# USB.net
KiCad netlist of a schematic drawn in EasyEDA Pro
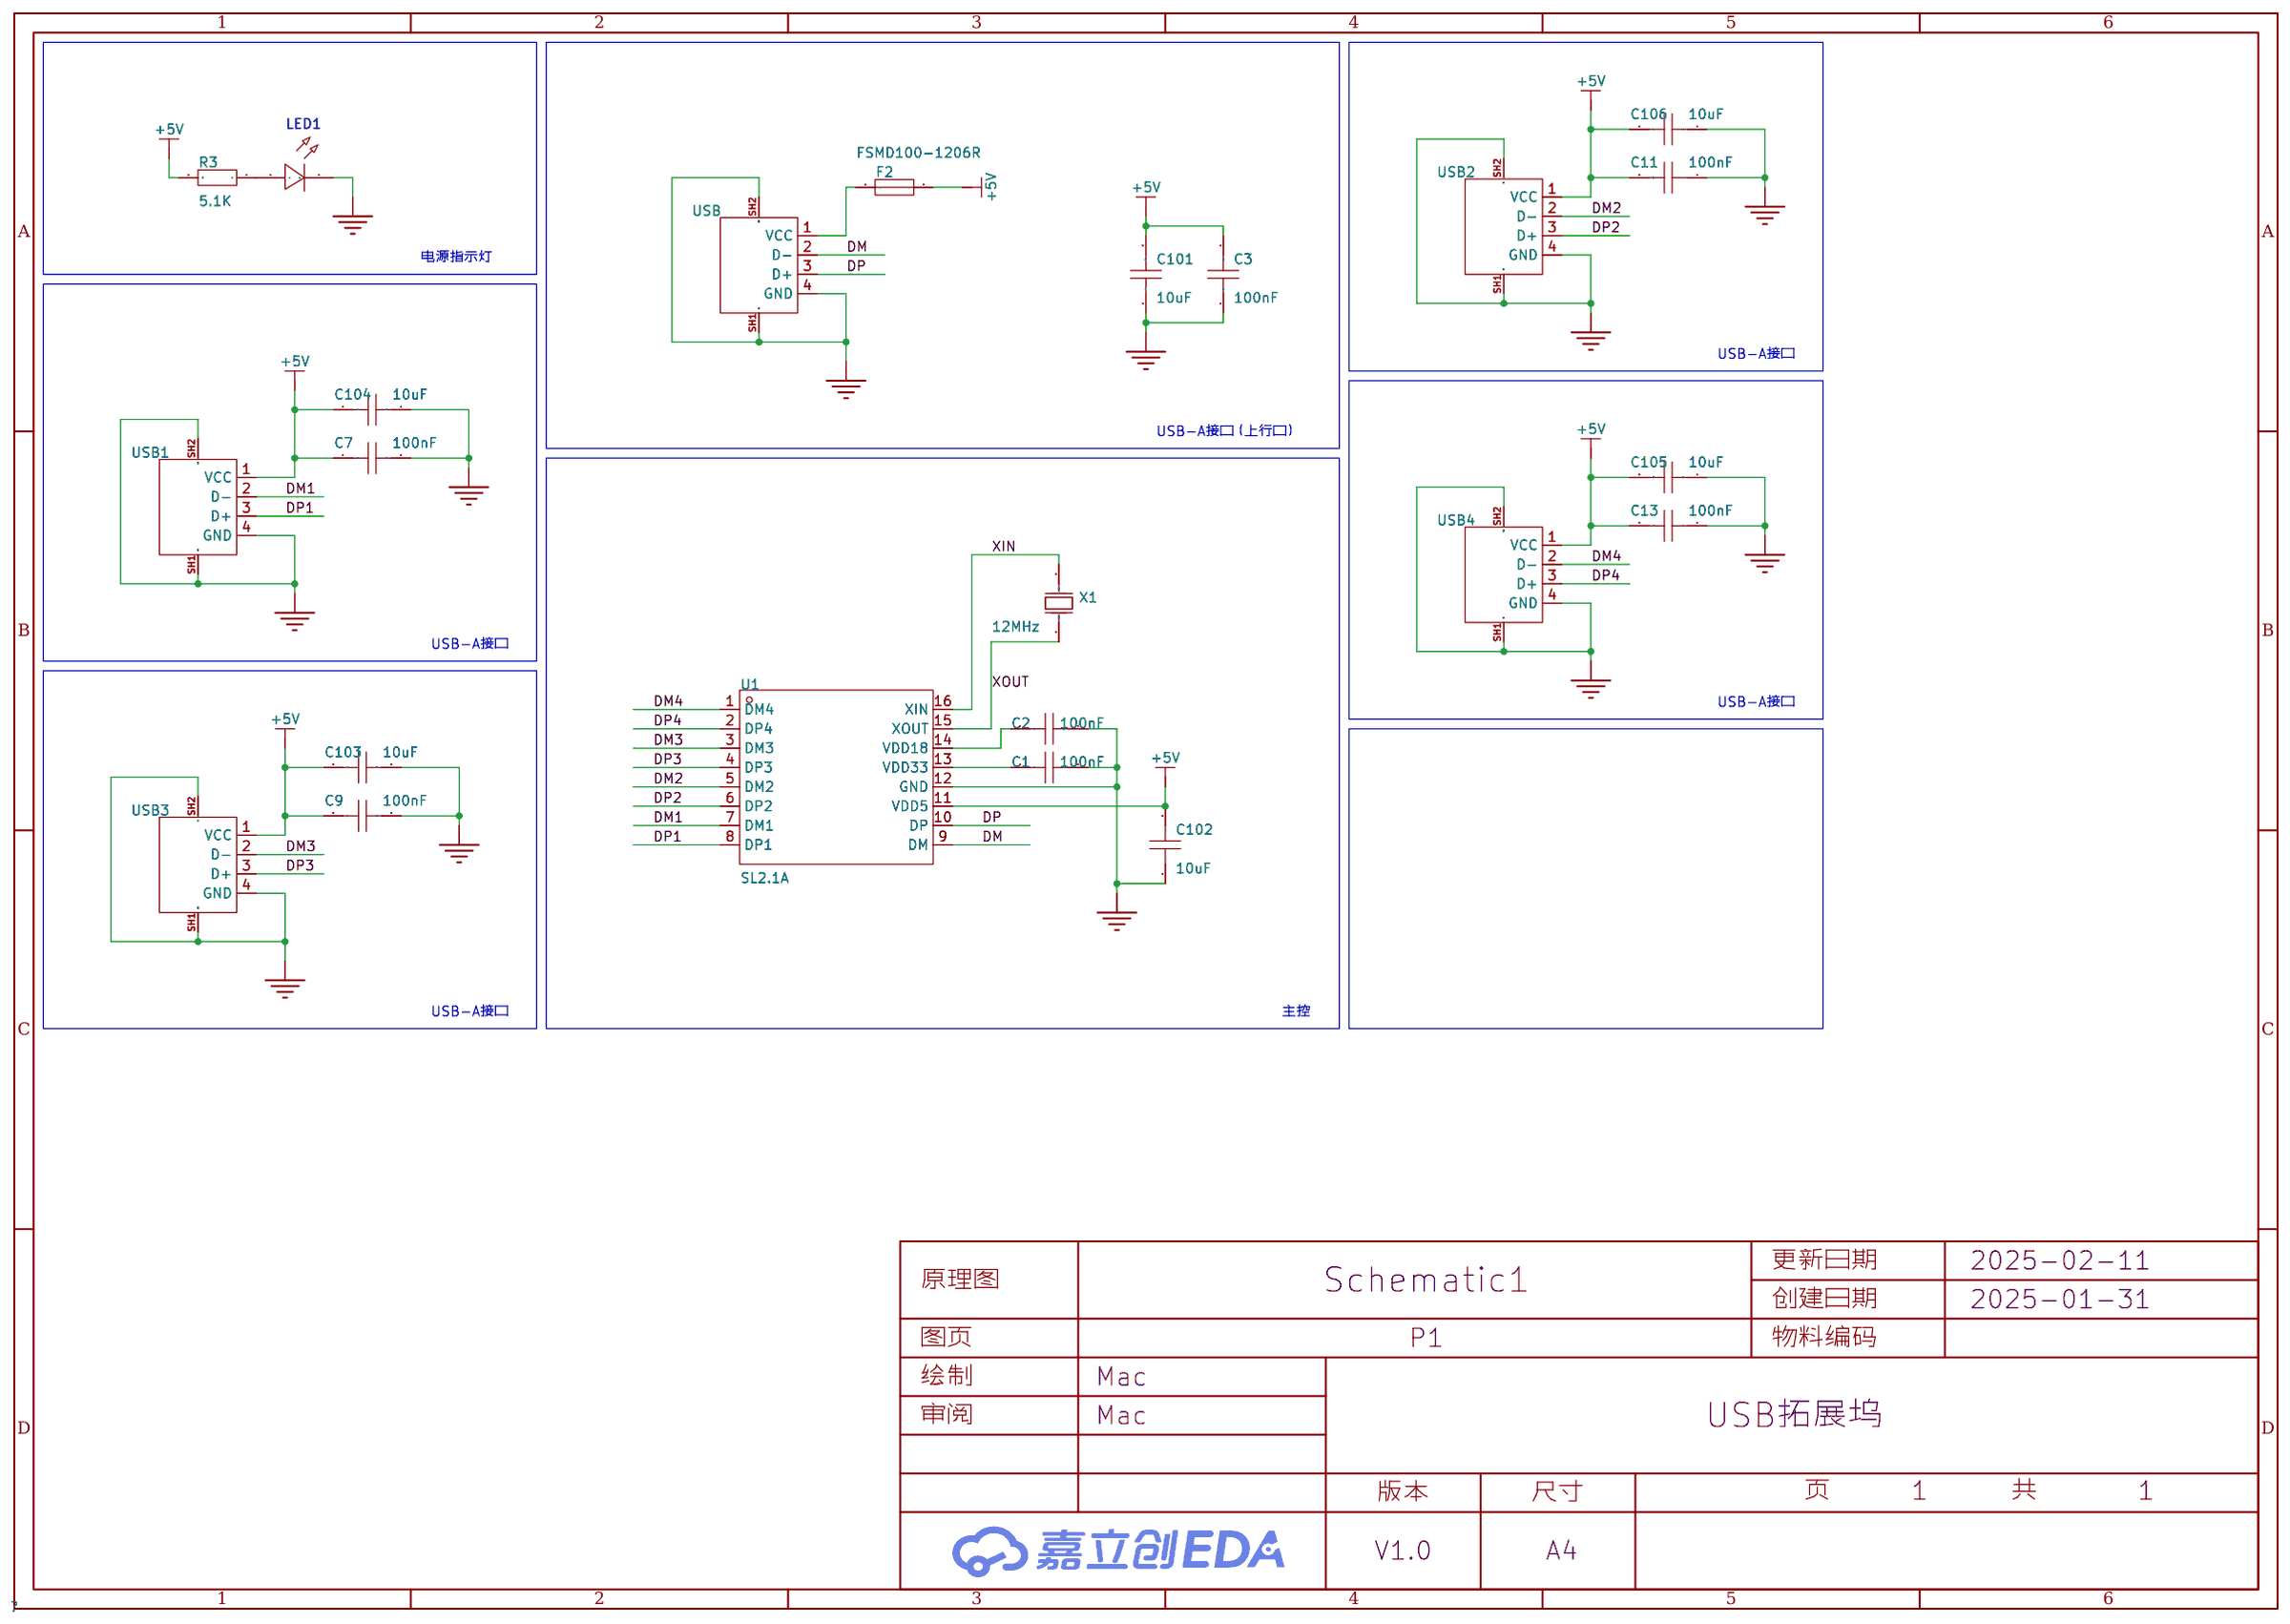
[diagram p0: schematic sheet]

(export (version "E")
  (design (tool "Eeschema 10.0.6"))
  (components
    (comp (ref "C1")
      (value "100nF")
      (footprint "easyedapro:C0603")
      (libsource (lib "easyedapro") (part "CapAcitance"))
    )
    (comp (ref "C2")
      (value "100nF")
      (footprint "easyedapro:C0603")
      (libsource (lib "easyedapro") (part "CapAcitance"))
    )
    (comp (ref "C3")
      (value "100nF")
      (footprint "easyedapro:C0603")
      (libsource (lib "easyedapro") (part "CapAcitance"))
    )
    (comp (ref "C7")
      (value "100nF")
      (footprint "easyedapro:C0603")
      (libsource (lib "easyedapro") (part "CapAcitance"))
    )
    (comp (ref "C9")
      (value "100nF")
      (footprint "easyedapro:C0603")
      (libsource (lib "easyedapro") (part "CapAcitance"))
    )
    (comp (ref "C11")
      (value "100nF")
      (footprint "easyedapro:C0603")
      (libsource (lib "easyedapro") (part "CapAcitance"))
    )
    (comp (ref "C13")
      (value "100nF")
      (footprint "easyedapro:C0603")
      (libsource (lib "easyedapro") (part "CapAcitance"))
    )
    (comp (ref "C101")
      (value "10uF")
      (footprint "easyedapro:C0603")
      (libsource (lib "easyedapro") (part "CapAcitance"))
    )
    (comp (ref "C102")
      (value "10uF")
      (footprint "easyedapro:C0603")
      (libsource (lib "easyedapro") (part "CapAcitance"))
    )
    (comp (ref "C103")
      (value "10uF")
      (footprint "easyedapro:C0603")
      (libsource (lib "easyedapro") (part "CapAcitance"))
    )
    (comp (ref "C104")
      (value "10uF")
      (footprint "easyedapro:C0603")
      (libsource (lib "easyedapro") (part "CapAcitance"))
    )
    (comp (ref "C105")
      (value "10uF")
      (footprint "easyedapro:C0603")
      (libsource (lib "easyedapro") (part "CapAcitance"))
    )
    (comp (ref "C106")
      (value "10uF")
      (footprint "easyedapro:C0603")
      (libsource (lib "easyedapro") (part "CapAcitance"))
    )
    (comp (ref "F2")
      (value "FSMD100-1206R")
      (footprint "easyedapro:F1206")
      (description "最大电压:6V;最大电流:100A;保持电流:1A;跳闸电流:1.8A;")
      (fields (field (name "Manufacturer") "FUZETEC(富致)"))
      (libsource (lib "easyedapro") (part "FSMD100-1206R"))
    )
    (comp (ref "LED1")
      (value "~")
      (footprint "easyedapro:LED_0603")
      (libsource (lib "easyedapro") (part "LED_G"))
    )
    (comp (ref "R3") (value "5.1K") (footprint "easyedapro:R0603") (libsource (lib "easyedapro") (part "电阻")))
    (comp (ref "U1")
      (value "SL2.1A")
      (footprint "easyedapro:SOP-16_L10.0-W3.9-P1.27-LS6.0-BL")
      (description "应用功能:集线器;接口协议:-;")
      (fields (field (name "Manufacturer") "CoreChips(和芯润德)"))
      (libsource (lib "easyedapro") (part "SL2.1A"))
    )
    (comp (ref "USB")
      (value "~")
      (footprint "easyedapro:USB_ Type-A")
      (libsource (lib "easyedapro") (part "USB_Type-A"))
    )
    (comp (ref "USB1")
      (value "~")
      (footprint "easyedapro:USB_ Type-A")
      (libsource (lib "easyedapro") (part "USB_Type-A"))
    )
    (comp (ref "USB2")
      (value "~")
      (footprint "easyedapro:USB_ Type-A")
      (libsource (lib "easyedapro") (part "USB_Type-A"))
    )
    (comp (ref "USB3")
      (value "~")
      (footprint "easyedapro:USB_ Type-A")
      (libsource (lib "easyedapro") (part "USB_Type-A"))
    )
    (comp (ref "USB4")
      (value "~")
      (footprint "easyedapro:USB_ Type-A")
      (libsource (lib "easyedapro") (part "USB_Type-A"))
    )
    (comp (ref "X1")
      (value "12MHz")
      (footprint "easyedapro:HC-49US_L11.5-W4.5-P4.88")
      (description "晶振类型:直插晶振;频率:12MHz;常温频差:±20ppm;外接负载电容:20pF;频率稳定度(全温):±30ppm;")
      (fields (field (name "Manufacturer Part") "X49SD12MSD2SC") (field (name "Manufacturer") "YXC(扬兴晶振)"))
      (libsource (lib "easyedapro") (part "X49SD12MSD2SC"))
    )
  )
  (nets
    (net (code "1") (name "+5V") (class "Default")
      (node (ref "C101") (pin "2") (pinfunction "2_2") (pintype "input"))
      (node (ref "C102") (pin "2") (pinfunction "2_2") (pintype "input"))
      (node (ref "C103") (pin "2") (pinfunction "2_2") (pintype "input"))
      (node (ref "C104") (pin "2") (pinfunction "2_2") (pintype "input"))
      (node (ref "C105") (pin "2") (pinfunction "2_2") (pintype "input"))
      (node (ref "C106") (pin "2") (pinfunction "2_2") (pintype "input"))
      (node (ref "C11") (pin "2") (pinfunction "2_2") (pintype "input"))
      (node (ref "C13") (pin "2") (pinfunction "2_2") (pintype "input"))
      (node (ref "C3") (pin "2") (pinfunction "2_2") (pintype "input"))
      (node (ref "C7") (pin "2") (pinfunction "2_2") (pintype "input"))
      (node (ref "C9") (pin "2") (pinfunction "2_2") (pintype "input"))
      (node (ref "F2") (pin "1") (pinfunction "1_1") (pintype "unspecified"))
      (node (ref "R3") (pin "2") (pinfunction "2_2") (pintype "input"))
      (node (ref "U1") (pin "11") (pinfunction "VDD5_11") (pintype "unspecified"))
      (node (ref "USB1") (pin "1") (pinfunction "VCC_1") (pintype "input"))
      (node (ref "USB2") (pin "1") (pinfunction "VCC_1") (pintype "input"))
      (node (ref "USB3") (pin "1") (pinfunction "VCC_1") (pintype "input"))
      (node (ref "USB4") (pin "1") (pinfunction "VCC_1") (pintype "input"))
    )
    (net (code "2") (name "/DM") (class "Default")
      (node (ref "U1") (pin "9") (pinfunction "DM_9") (pintype "unspecified"))
      (node (ref "USB") (pin "2") (pinfunction "D-_2") (pintype "input"))
    )
    (net (code "3") (name "/DM1") (class "Default")
      (node (ref "U1") (pin "7") (pinfunction "DM1_7") (pintype "unspecified"))
      (node (ref "USB1") (pin "2") (pinfunction "D-_2") (pintype "input"))
    )
    (net (code "4") (name "/DM2") (class "Default")
      (node (ref "U1") (pin "5") (pinfunction "DM2_5") (pintype "unspecified"))
      (node (ref "USB2") (pin "2") (pinfunction "D-_2") (pintype "input"))
    )
    (net (code "5") (name "/DM3") (class "Default")
      (node (ref "U1") (pin "3") (pinfunction "DM3_3") (pintype "unspecified"))
      (node (ref "USB3") (pin "2") (pinfunction "D-_2") (pintype "input"))
    )
    (net (code "6") (name "/DM4") (class "Default")
      (node (ref "U1") (pin "1") (pinfunction "DM4_1") (pintype "unspecified"))
      (node (ref "USB4") (pin "2") (pinfunction "D-_2") (pintype "input"))
    )
    (net (code "7") (name "/DP") (class "Default")
      (node (ref "U1") (pin "10") (pinfunction "DP_10") (pintype "unspecified"))
      (node (ref "USB") (pin "3") (pinfunction "D+_3") (pintype "input"))
    )
    (net (code "8") (name "/DP1") (class "Default")
      (node (ref "U1") (pin "8") (pinfunction "DP1_8") (pintype "unspecified"))
      (node (ref "USB1") (pin "3") (pinfunction "D+_3") (pintype "input"))
    )
    (net (code "9") (name "/DP2") (class "Default")
      (node (ref "U1") (pin "6") (pinfunction "DP2_6") (pintype "unspecified"))
      (node (ref "USB2") (pin "3") (pinfunction "D+_3") (pintype "input"))
    )
    (net (code "10") (name "/DP3") (class "Default")
      (node (ref "U1") (pin "4") (pinfunction "DP3_4") (pintype "unspecified"))
      (node (ref "USB3") (pin "3") (pinfunction "D+_3") (pintype "input"))
    )
    (net (code "11") (name "/DP4") (class "Default")
      (node (ref "U1") (pin "2") (pinfunction "DP4_2") (pintype "unspecified"))
      (node (ref "USB4") (pin "3") (pinfunction "D+_3") (pintype "input"))
    )
    (net (code "12") (name "/XIN") (class "Default")
      (node (ref "U1") (pin "16") (pinfunction "XIN_16") (pintype "unspecified"))
      (node (ref "X1") (pin "1") (pinfunction "OSC1_1") (pintype "input"))
    )
    (net (code "13") (name "/XOUT") (class "Default")
      (node (ref "U1") (pin "15") (pinfunction "XOUT_15") (pintype "unspecified"))
      (node (ref "X1") (pin "2") (pinfunction "OSC2_2") (pintype "input"))
    )
    (net (code "14") (name "GND") (class "Default")
      (node (ref "C1") (pin "2") (pinfunction "2_2") (pintype "input"))
      (node (ref "C101") (pin "1") (pinfunction "1_1") (pintype "input"))
      (node (ref "C102") (pin "1") (pinfunction "1_1") (pintype "input"))
      (node (ref "C103") (pin "1") (pinfunction "1_1") (pintype "input"))
      (node (ref "C104") (pin "1") (pinfunction "1_1") (pintype "input"))
      (node (ref "C105") (pin "1") (pinfunction "1_1") (pintype "input"))
      (node (ref "C106") (pin "1") (pinfunction "1_1") (pintype "input"))
      (node (ref "C11") (pin "1") (pinfunction "1_1") (pintype "input"))
      (node (ref "C13") (pin "1") (pinfunction "1_1") (pintype "input"))
      (node (ref "C2") (pin "2") (pinfunction "2_2") (pintype "input"))
      (node (ref "C3") (pin "1") (pinfunction "1_1") (pintype "input"))
      (node (ref "C7") (pin "1") (pinfunction "1_1") (pintype "input"))
      (node (ref "C9") (pin "1") (pinfunction "1_1") (pintype "input"))
      (node (ref "LED1") (pin "1") (pinfunction "C_1") (pintype "input"))
      (node (ref "U1") (pin "12") (pinfunction "GND_12") (pintype "unspecified"))
      (node (ref "USB") (pin "4") (pinfunction "GND_4") (pintype "input"))
      (node (ref "USB") (pin "SH1") (pinfunction "SH1_SH1") (pintype "input"))
      (node (ref "USB") (pin "SH2") (pinfunction "SH2_SH2") (pintype "input"))
      (node (ref "USB1") (pin "4") (pinfunction "GND_4") (pintype "input"))
      (node (ref "USB1") (pin "SH1") (pinfunction "SH1_SH1") (pintype "input"))
      (node (ref "USB1") (pin "SH2") (pinfunction "SH2_SH2") (pintype "input"))
      (node (ref "USB2") (pin "4") (pinfunction "GND_4") (pintype "input"))
      (node (ref "USB2") (pin "SH1") (pinfunction "SH1_SH1") (pintype "input"))
      (node (ref "USB2") (pin "SH2") (pinfunction "SH2_SH2") (pintype "input"))
      (node (ref "USB3") (pin "4") (pinfunction "GND_4") (pintype "input"))
      (node (ref "USB3") (pin "SH1") (pinfunction "SH1_SH1") (pintype "input"))
      (node (ref "USB3") (pin "SH2") (pinfunction "SH2_SH2") (pintype "input"))
      (node (ref "USB4") (pin "4") (pinfunction "GND_4") (pintype "input"))
      (node (ref "USB4") (pin "SH1") (pinfunction "SH1_SH1") (pintype "input"))
      (node (ref "USB4") (pin "SH2") (pinfunction "SH2_SH2") (pintype "input"))
    )
    (net (code "15") (name "Net-(LED1-A)") (class "Default")
      (node (ref "LED1") (pin "2") (pinfunction "A_2") (pintype "input"))
      (node (ref "R3") (pin "1") (pinfunction "1_1") (pintype "input"))
    )
    (net (code "16") (name "Net-(U1-VDD18)") (class "Default")
      (node (ref "C2") (pin "1") (pinfunction "1_1") (pintype "input"))
      (node (ref "U1") (pin "14") (pinfunction "VDD18_14") (pintype "unspecified"))
    )
    (net (code "17") (name "Net-(U1-VDD33)") (class "Default")
      (node (ref "C1") (pin "1") (pinfunction "1_1") (pintype "input"))
      (node (ref "U1") (pin "13") (pinfunction "VDD33_13") (pintype "unspecified"))
    )
    (net (code "18") (name "Net-(USB-VCC)") (class "Default")
      (node (ref "F2") (pin "2") (pinfunction "2_2") (pintype "unspecified"))
      (node (ref "USB") (pin "1") (pinfunction "VCC_1") (pintype "input"))
    )
  )
)
